# indication.net
KiCad netlist of a schematic drawn in Altium Designer
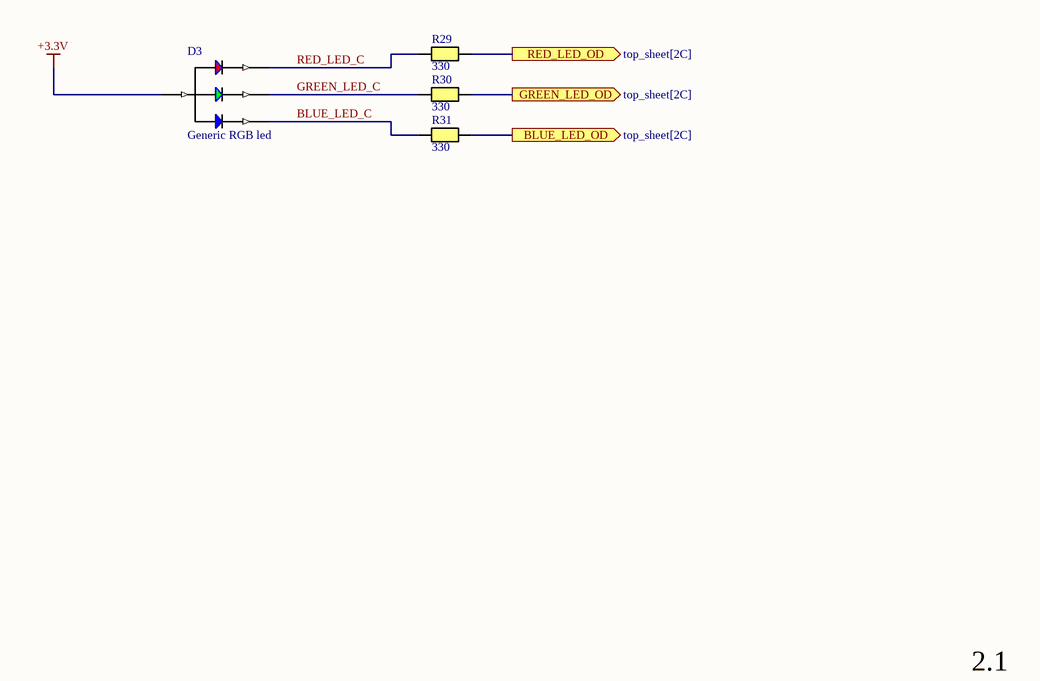
[diagram p0: indication.SchDoc]

(export (version "E")
  (design (tool "Eeschema 10.0.6"))
  (components
    (comp (ref "D3")
      (value "Generic RGB led")
      (footprint "RGB throu hole 90 deg")
      (libsource (lib "Optical") (part "RGB led"))
    )
    (comp (ref "R29")
      (value "330")
      (footprint "RESC0603(1608)_N")
      (description "Resistor Medium Density")
      (libsource (lib "Discrete") (part "Resistor M"))
    )
    (comp (ref "R30")
      (value "330")
      (footprint "RESC0603(1608)_N")
      (description "Resistor Medium Density")
      (libsource (lib "Discrete") (part "Resistor M"))
    )
    (comp (ref "R31")
      (value "330")
      (footprint "RESC0603(1608)_N")
      (description "Resistor Medium Density")
      (libsource (lib "Discrete") (part "Resistor M"))
    )
  )
  (nets
    (net (code "1") (name "+3.3V") (class "Default")
      (node (ref "D3") (pin "CA") (pinfunction "CA_CA") (pintype "input"))
    )
    (net (code "2") (name "/BLUE_LED_C") (class "Default")
      (node (ref "D3") (pin "BC") (pinfunction "BC_BC") (pintype "output"))
      (node (ref "R31") (pin "1") (pinfunction "1_1") (pintype "passive"))
    )
    (net (code "3") (name "/BLUE_LED_OD") (class "Default")
      (node (ref "R31") (pin "2") (pinfunction "2_2") (pintype "passive"))
    )
    (net (code "4") (name "/GREEN_LED_C") (class "Default")
      (node (ref "D3") (pin "GC") (pinfunction "GC_GC") (pintype "output"))
      (node (ref "R30") (pin "1") (pinfunction "1_1") (pintype "passive"))
    )
    (net (code "5") (name "/GREEN_LED_OD") (class "Default")
      (node (ref "R30") (pin "2") (pinfunction "2_2") (pintype "passive"))
    )
    (net (code "6") (name "/RED_LED_C") (class "Default")
      (node (ref "D3") (pin "RC") (pinfunction "RC_RC") (pintype "output"))
      (node (ref "R29") (pin "1") (pinfunction "1_1") (pintype "passive"))
    )
    (net (code "7") (name "/RED_LED_OD") (class "Default")
      (node (ref "R29") (pin "2") (pinfunction "2_2") (pintype "passive"))
    )
  )
)
